# WirelessNRF24.net
KiCad netlist of a schematic drawn in EAGLE
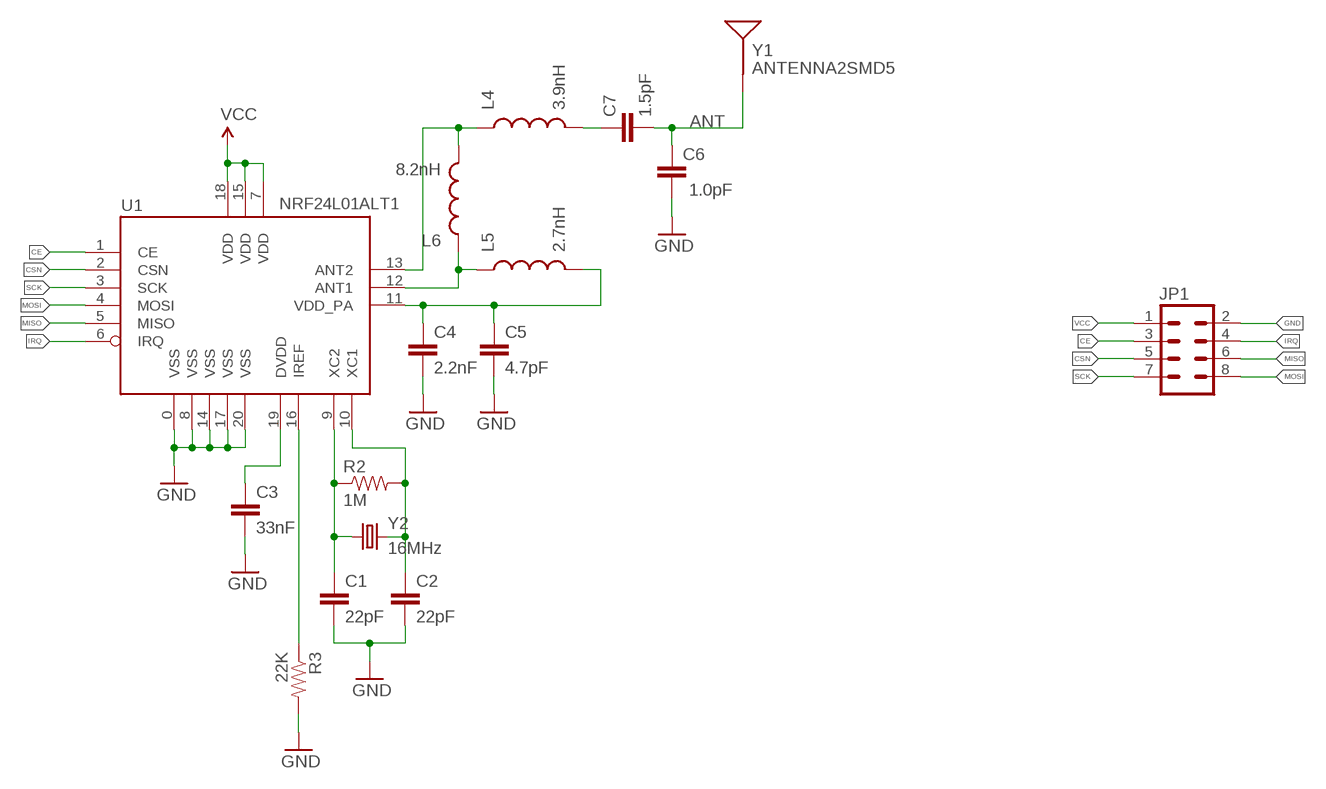
[diagram p0: schematic, sheet 1]

(export (version "E")
  (design (tool "Eeschema 10.0.6"))
  (components
    (comp (ref "C1")
      (value "22pF")
      (footprint "eagle-import:0603-CAP")
      (libsource (lib "eagle-import") (part "CAP0603-CAP"))
    )
    (comp (ref "C2")
      (value "22pF")
      (footprint "eagle-import:0603-CAP")
      (libsource (lib "eagle-import") (part "CAP0603-CAP"))
    )
    (comp (ref "C3")
      (value "33nF")
      (footprint "eagle-import:0603-CAP")
      (libsource (lib "eagle-import") (part "CAP0603-CAP"))
    )
    (comp (ref "C4")
      (value "2.2nF")
      (footprint "eagle-import:0603-CAP")
      (libsource (lib "eagle-import") (part "CAP0603-CAP"))
    )
    (comp (ref "C5")
      (value "4.7pF")
      (footprint "eagle-import:0603-CAP")
      (libsource (lib "eagle-import") (part "CAP0603-CAP"))
    )
    (comp (ref "C6")
      (value "1.0pF")
      (footprint "eagle-import:0603-CAP")
      (libsource (lib "eagle-import") (part "CAP0603-CAP"))
    )
    (comp (ref "C7")
      (value "1.5pF")
      (footprint "eagle-import:0603-CAP")
      (libsource (lib "eagle-import") (part "CAP0603-CAP"))
    )
    (comp (ref "JP1")
      (value "M04X2_0.05\"")
      (footprint "eagle-import:M04X2_0.05_")
      (libsource (lib "eagle-import") (part "M04X2_0.05{dblquote}"))
    )
    (comp (ref "L4")
      (value "3.9nH")
      (footprint "eagle-import:0603")
      (libsource (lib "eagle-import") (part "INDUCTOR0603"))
    )
    (comp (ref "L5")
      (value "2.7nH")
      (footprint "eagle-import:0603")
      (libsource (lib "eagle-import") (part "INDUCTOR0603"))
    )
    (comp (ref "L6")
      (value "8.2nH")
      (footprint "eagle-import:0603")
      (libsource (lib "eagle-import") (part "INDUCTOR0603"))
    )
    (comp (ref "R2")
      (value "1M")
      (footprint "eagle-import:0603-RES")
      (libsource (lib "eagle-import") (part "RESISTOR0603-RES"))
    )
    (comp (ref "R3")
      (value "22K")
      (footprint "eagle-import:0603-RES")
      (libsource (lib "eagle-import") (part "RESISTOR0603-RES"))
    )
    (comp (ref "U1")
      (value "NRF24L01ALT1")
      (footprint "eagle-import:QFN20_ALT1")
      (libsource (lib "eagle-import") (part "NRF24L01ALT1"))
    )
    (comp (ref "Y1")
      (value "ANTENNA2SMD5")
      (footprint "eagle-import:ANTENNA-CHIP5")
      (libsource (lib "eagle-import") (part "ANTENNA2SMD5"))
    )
    (comp (ref "Y2")
      (value "16MHz")
      (footprint "eagle-import:CRYSTAL-TXC-7A")
      (libsource (lib "eagle-import") (part "CRYSTALTXC-7A"))
    )
  )
  (nets
    (net (code "1") (name "/ANT") (class "Default")
      (node (ref "C6") (pin "2") (pinfunction "2_2") (pintype "passive"))
      (node (ref "C7") (pin "2") (pinfunction "2_2") (pintype "passive"))
      (node (ref "Y1") (pin "FEED") (pinfunction "SIGNAL_FEED") (pintype "bidirectional"))
    )
    (net (code "2") (name "CE") (class "Default")
      (node (ref "JP1") (pin "3") (pinfunction "3_3") (pintype "passive"))
      (node (ref "U1") (pin "1") (pinfunction "CE_1") (pintype "input"))
    )
    (net (code "3") (name "CSN") (class "Default")
      (node (ref "JP1") (pin "5") (pinfunction "5_5") (pintype "passive"))
      (node (ref "U1") (pin "2") (pinfunction "CSN_2") (pintype "input"))
    )
    (net (code "4") (name "GND") (class "Default")
      (node (ref "C1") (pin "2") (pinfunction "2_2") (pintype "passive"))
      (node (ref "C2") (pin "2") (pinfunction "2_2") (pintype "passive"))
      (node (ref "C3") (pin "2") (pinfunction "2_2") (pintype "passive"))
      (node (ref "C4") (pin "2") (pinfunction "2_2") (pintype "passive"))
      (node (ref "C5") (pin "2") (pinfunction "2_2") (pintype "passive"))
      (node (ref "C6") (pin "1") (pinfunction "1_1") (pintype "passive"))
      (node (ref "JP1") (pin "2") (pinfunction "2_2") (pintype "passive"))
      (node (ref "R3") (pin "2") (pinfunction "2_2") (pintype "passive"))
      (node (ref "U1") (pin "0") (pinfunction "VSS_0") (pintype "power_in"))
      (node (ref "U1") (pin "14") (pinfunction "VSS_14") (pintype "power_in"))
      (node (ref "U1") (pin "17") (pinfunction "VSS_17") (pintype "power_in"))
      (node (ref "U1") (pin "20") (pinfunction "VSS_20") (pintype "power_in"))
      (node (ref "U1") (pin "8") (pinfunction "VSS_8") (pintype "power_in"))
    )
    (net (code "5") (name "IRQ") (class "Default")
      (node (ref "JP1") (pin "4") (pinfunction "4_4") (pintype "passive"))
      (node (ref "U1") (pin "6") (pinfunction "IRQ_6") (pintype "output"))
    )
    (net (code "6") (name "MISO") (class "Default")
      (node (ref "JP1") (pin "6") (pinfunction "6_6") (pintype "passive"))
      (node (ref "U1") (pin "5") (pinfunction "MISO_5") (pintype "output"))
    )
    (net (code "7") (name "MOSI") (class "Default")
      (node (ref "JP1") (pin "8") (pinfunction "8_8") (pintype "passive"))
      (node (ref "U1") (pin "4") (pinfunction "MOSI_4") (pintype "input"))
    )
    (net (code "8") (name "Net-(C7-Pad1)") (class "Default")
      (node (ref "C7") (pin "1") (pinfunction "1_1") (pintype "passive"))
      (node (ref "L4") (pin "2") (pinfunction "2_2") (pintype "passive"))
    )
    (net (code "9") (name "Net-(U1-ANT1)") (class "Default")
      (node (ref "L5") (pin "1") (pinfunction "1_1") (pintype "passive"))
      (node (ref "L6") (pin "1") (pinfunction "1_1") (pintype "passive"))
      (node (ref "U1") (pin "12") (pinfunction "ANT1_12") (pintype "output"))
    )
    (net (code "10") (name "Net-(U1-ANT2)") (class "Default")
      (node (ref "L4") (pin "1") (pinfunction "1_1") (pintype "passive"))
      (node (ref "L6") (pin "2") (pinfunction "2_2") (pintype "passive"))
      (node (ref "U1") (pin "13") (pinfunction "ANT2_13") (pintype "output"))
    )
    (net (code "11") (name "Net-(U1-DVDD)") (class "Default")
      (node (ref "C3") (pin "1") (pinfunction "1_1") (pintype "passive"))
      (node (ref "U1") (pin "19") (pinfunction "DVDD_19") (pintype "power_in"))
    )
    (net (code "12") (name "Net-(U1-IREF)") (class "Default")
      (node (ref "R3") (pin "1") (pinfunction "1_1") (pintype "passive"))
      (node (ref "U1") (pin "16") (pinfunction "IREF_16") (pintype "input"))
    )
    (net (code "13") (name "Net-(U1-VDD_PA)") (class "Default")
      (node (ref "C4") (pin "1") (pinfunction "1_1") (pintype "passive"))
      (node (ref "C5") (pin "1") (pinfunction "1_1") (pintype "passive"))
      (node (ref "L5") (pin "2") (pinfunction "2_2") (pintype "passive"))
      (node (ref "U1") (pin "11") (pinfunction "VDD_PA_11") (pintype "power_in"))
    )
    (net (code "14") (name "Net-(U1-XC1)") (class "Default")
      (node (ref "C2") (pin "1") (pinfunction "1_1") (pintype "passive"))
      (node (ref "R2") (pin "2") (pinfunction "2_2") (pintype "passive"))
      (node (ref "U1") (pin "10") (pinfunction "XC1_10") (pintype "input"))
      (node (ref "Y2") (pin "P$2") (pinfunction "2_P$2") (pintype "passive"))
    )
    (net (code "15") (name "Net-(U1-XC2)") (class "Default")
      (node (ref "C1") (pin "1") (pinfunction "1_1") (pintype "passive"))
      (node (ref "R2") (pin "1") (pinfunction "1_1") (pintype "passive"))
      (node (ref "U1") (pin "9") (pinfunction "XC2_9") (pintype "input"))
      (node (ref "Y2") (pin "P$1") (pinfunction "1_P$1") (pintype "passive"))
    )
    (net (code "16") (name "SCK") (class "Default")
      (node (ref "JP1") (pin "7") (pinfunction "7_7") (pintype "passive"))
      (node (ref "U1") (pin "3") (pinfunction "SCK_3") (pintype "input"))
    )
    (net (code "17") (name "VCC") (class "Default")
      (node (ref "JP1") (pin "1") (pinfunction "1_1") (pintype "passive"))
      (node (ref "U1") (pin "15") (pinfunction "VDD_15") (pintype "power_in"))
      (node (ref "U1") (pin "18") (pinfunction "VDD_18") (pintype "power_in"))
      (node (ref "U1") (pin "7") (pinfunction "VDD_7") (pintype "power_in"))
    )
  )
)
